# overview.net
KiCad netlist of a schematic drawn in Altium Designer
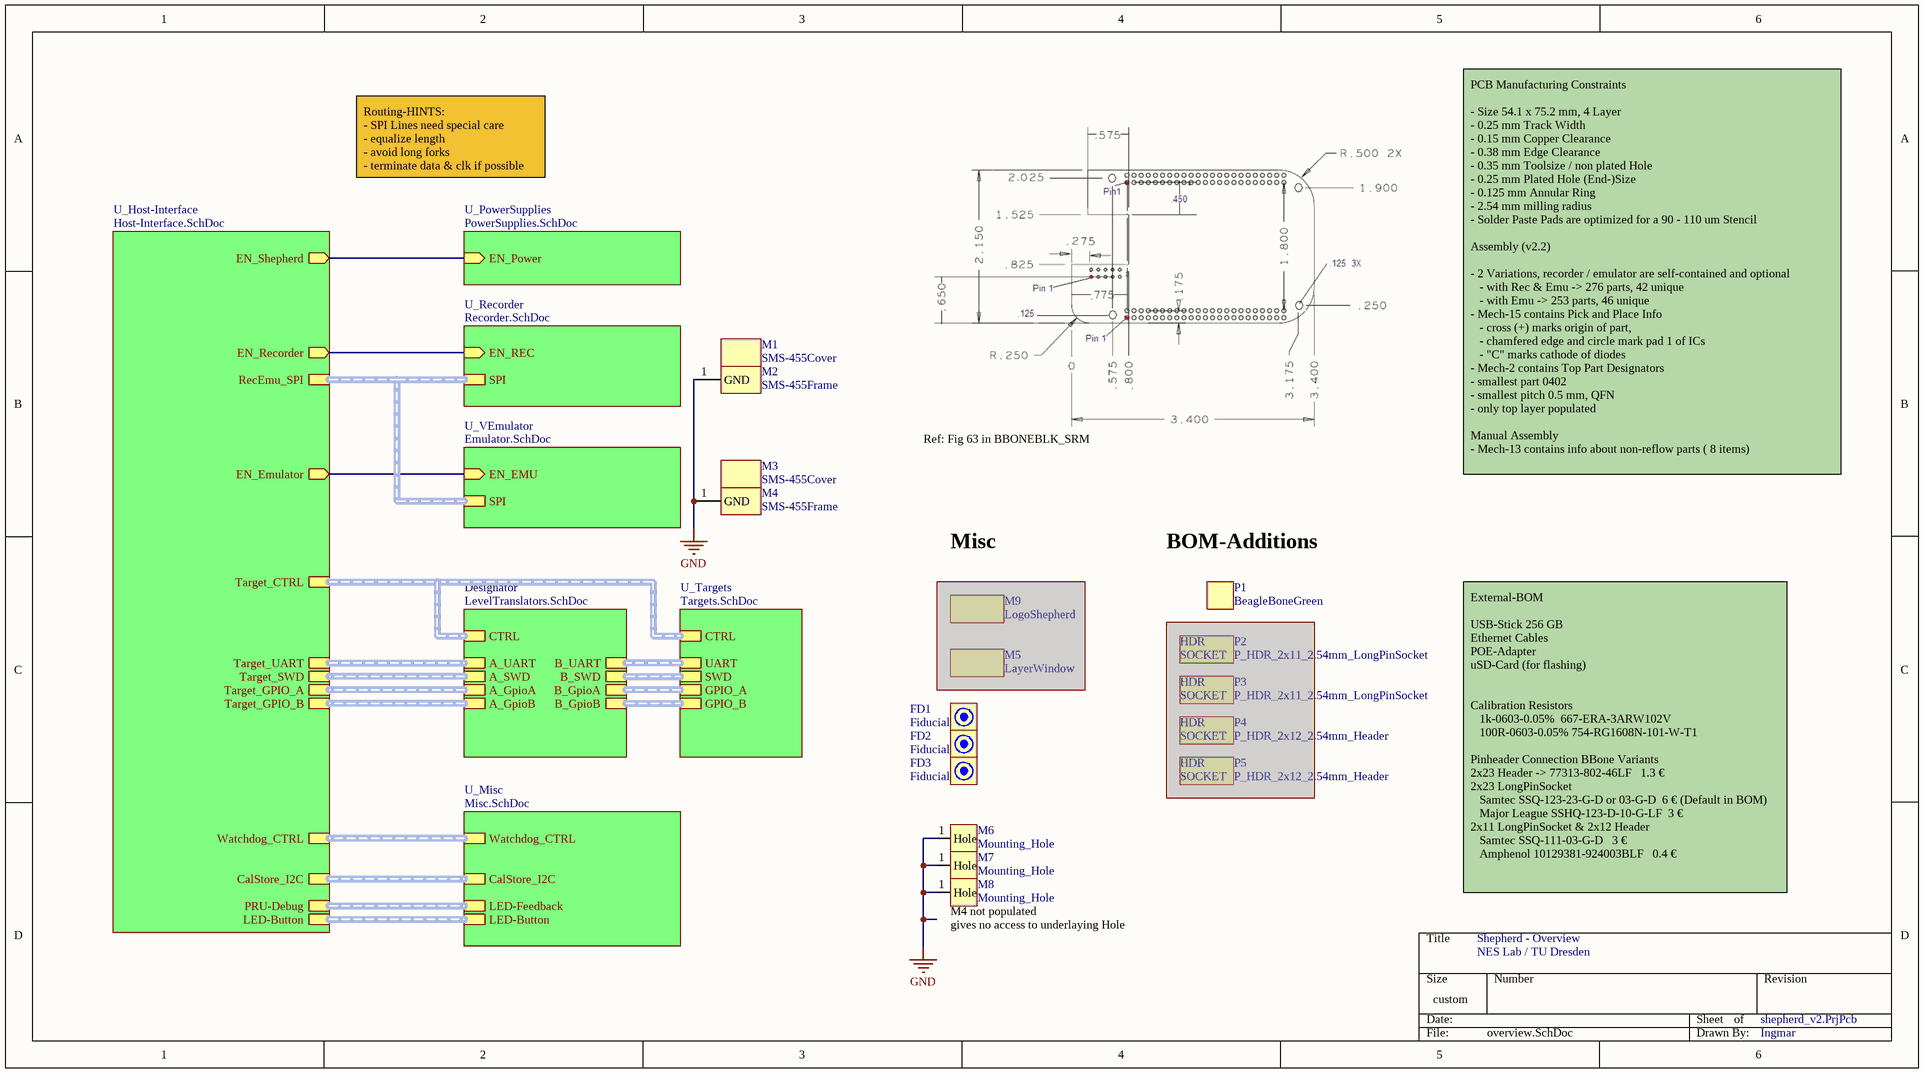
[diagram p0: overview.SchDoc]

(export (version "E")
  (design (tool "Eeschema 10.0.6"))
  (components
    (comp (ref "FD1")
      (value "Fiducial")
      (footprint "M_Fiducial_3mm")
      (libsource (lib "shepherd_parts") (part "Fiducial"))
    )
    (comp (ref "FD2")
      (value "Fiducial")
      (footprint "M_Fiducial_3mm")
      (libsource (lib "shepherd_parts") (part "Fiducial"))
    )
    (comp (ref "FD3")
      (value "Fiducial")
      (footprint "M_Fiducial_3mm")
      (libsource (lib "shepherd_parts") (part "Fiducial"))
    )
    (comp (ref "M1")
      (value "SMS-455Cover")
      (description "EMI-Shield Cover, SMT, .75\"x.75\", 18x18mm, Height 5.08 mm, ~40-70 dB")
      (fields (field (name "MANUFACTURER") "LeaderTech"))
      (libsource (lib "shepherd_parts") (part "SMS-455Cover"))
    )
    (comp (ref "M2")
      (value "SMS-455Frame")
      (footprint "SMS-455F")
      (description "EMI-Shield Frame, SMT, .75\"x.75\", 18x18mm, Height 5.08 mm, ~40-70 dB")
      (fields (field (name "MANUFACTURER") "LeaderTech"))
      (libsource (lib "shepherd_parts") (part "SMS-455Frame"))
    )
    (comp (ref "M3")
      (value "SMS-455Cover")
      (description "EMI-Shield Cover, SMT, .75\"x.75\", 18x18mm, Height 5.08 mm, ~40-70 dB")
      (fields (field (name "MANUFACTURER") "LeaderTech"))
      (libsource (lib "shepherd_parts") (part "SMS-455Cover"))
    )
    (comp (ref "M4")
      (value "SMS-455Frame")
      (footprint "SMS-455F")
      (description "EMI-Shield Frame, SMT, .75\"x.75\", 18x18mm, Height 5.08 mm, ~40-70 dB")
      (fields (field (name "MANUFACTURER") "LeaderTech"))
      (libsource (lib "shepherd_parts") (part "SMS-455Frame"))
    )
    (comp (ref "M5")
      (value "LayerWindow")
      (footprint "LayerWindow_4L_EC_conform_B")
      (libsource (lib "shepherd_parts") (part "LayerWindow"))
    )
    (comp (ref "M6")
      (value "Mounting_Hole")
      (footprint "M_Mountinghole_3.2mm")
      (libsource (lib "shepherd_parts") (part "Mounting_Hole"))
    )
    (comp (ref "M7")
      (value "Mounting_Hole")
      (footprint "M_Mountinghole_3.2mm_min")
      (libsource (lib "shepherd_parts") (part "Mounting_Hole"))
    )
    (comp (ref "M8")
      (value "Mounting_Hole")
      (footprint "M_Mountinghole_3.2mm_min")
      (libsource (lib "shepherd_parts") (part "Mounting_Hole"))
    )
    (comp (ref "M9")
      (value "LogoShepherd")
      (footprint "LogoShepherd")
      (libsource (lib "shepherd_parts") (part "LogoShepherd"))
    )
    (comp (ref "P1")
      (value "BeagleBoneGreen")
      (fields (field (name "MANUFACTURER") "Seeed Studio"))
      (libsource (lib "shepherd_parts") (part "BeagleBoneGreen"))
    )
    (comp (ref "P2")
      (value "P_HDR_2x11_2.54mm_LongPinSocket")
      (description "10 mm Tail length")
      (fields (field (name "MANUFACTURER") "Samtec"))
      (libsource (lib "shepherd_parts") (part ".P_HDR_2x11_2.54mm_LongPinSocket"))
    )
    (comp (ref "P3")
      (value "P_HDR_2x11_2.54mm_LongPinSocket")
      (description "10 mm Tail length")
      (fields (field (name "MANUFACTURER") "Samtec"))
      (libsource (lib "shepherd_parts") (part ".P_HDR_2x11_2.54mm_LongPinSocket"))
    )
    (comp (ref "P4")
      (value "P_HDR_2x12_2.54mm_Header")
      (fields (field (name "MANUFACTURER") "Amphenol FCI"))
      (libsource (lib "shepherd_parts") (part ".P_HDR_2x12_2.54mm_Header"))
    )
    (comp (ref "P5")
      (value "P_HDR_2x12_2.54mm_Header")
      (fields (field (name "MANUFACTURER") "Amphenol FCI"))
      (libsource (lib "shepherd_parts") (part ".P_HDR_2x12_2.54mm_Header"))
    )
  )
  (nets
    (net (code "18") (name "GND") (class "Default")
      (node (ref "M2") (pin "1") (pinfunction "GND_1") (pintype "power_in"))
      (node (ref "M4") (pin "1") (pinfunction "GND_1") (pintype "power_in"))
      (node (ref "M6") (pin "1") (pinfunction "Hole_1") (pintype "passive"))
      (node (ref "M7") (pin "1") (pinfunction "Hole_1") (pintype "passive"))
      (node (ref "M8") (pin "1") (pinfunction "Hole_1") (pintype "passive"))
    )
  )
)
